# Data_Cable_REPLACMENT.net
KiCad netlist of a schematic drawn in EAGLE
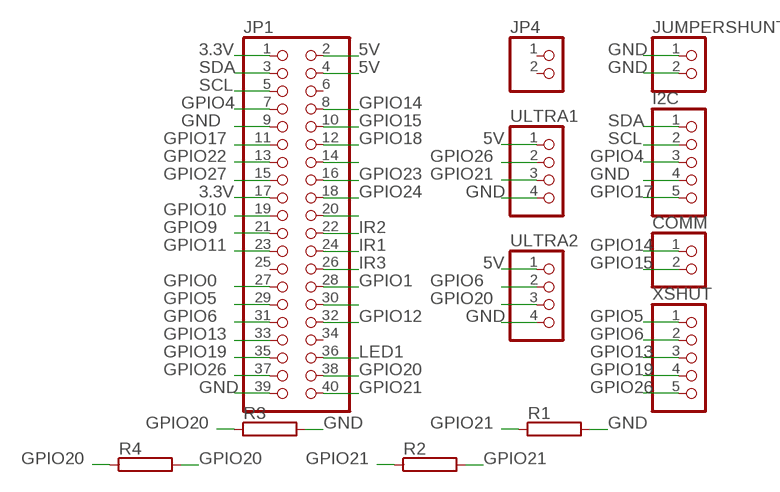
[diagram p0: schematic, sheet 1]

(export (version "E")
  (design (tool "Eeschema 10.0.6"))
  (components
    (comp (ref "COMM")
      (value "PINHD-1X2")
      (footprint "eagle-import:1X02")
      (libsource (lib "eagle-import") (part "PINHD-1X2"))
    )
    (comp (ref "I2C")
      (value "PINHD-1X5")
      (footprint "eagle-import:1X05")
      (libsource (lib "eagle-import") (part "PINHD-1X5"))
    )
    (comp (ref "JP1")
      (value "PINHD-2X20")
      (footprint "eagle-import:2X20")
      (libsource (lib "eagle-import") (part "PINHD-2X20"))
    )
    (comp (ref "JP4")
      (value "PINHD-1X2")
      (footprint "eagle-import:1X02")
      (libsource (lib "eagle-import") (part "PINHD-1X2"))
    )
    (comp (ref "JUMPERSHUNT")
      (value "PINHD-1X2")
      (footprint "eagle-import:1X02")
      (libsource (lib "eagle-import") (part "PINHD-1X2"))
    )
    (comp (ref "R1")
      (value "RHPS58")
      (footprint "eagle-import:HPS58")
      (libsource (lib "eagle-import") (part "RHPS58"))
    )
    (comp (ref "R2")
      (value "RHPS58")
      (footprint "eagle-import:HPS58")
      (libsource (lib "eagle-import") (part "RHPS58"))
    )
    (comp (ref "R3")
      (value "RHPS58")
      (footprint "eagle-import:HPS58")
      (libsource (lib "eagle-import") (part "RHPS58"))
    )
    (comp (ref "R4")
      (value "RHPS58")
      (footprint "eagle-import:HPS58")
      (libsource (lib "eagle-import") (part "RHPS58"))
    )
    (comp (ref "ULTRA1")
      (value "PINHD-1X4")
      (footprint "eagle-import:1X04")
      (libsource (lib "eagle-import") (part "PINHD-1X4"))
    )
    (comp (ref "ULTRA2")
      (value "PINHD-1X4")
      (footprint "eagle-import:1X04")
      (libsource (lib "eagle-import") (part "PINHD-1X4"))
    )
    (comp (ref "XSHUT")
      (value "PINHD-1X5")
      (footprint "eagle-import:1X05")
      (libsource (lib "eagle-import") (part "PINHD-1X5"))
    )
  )
  (nets
    (net (code "1") (name "/3.3V") (class "Default")
      (node (ref "JP1") (pin "1") (pinfunction "1_1") (pintype "passive"))
      (node (ref "JP1") (pin "17") (pinfunction "17_17") (pintype "passive"))
    )
    (net (code "2") (name "/5V") (class "Default")
      (node (ref "JP1") (pin "2") (pinfunction "2_2") (pintype "passive"))
      (node (ref "JP1") (pin "4") (pinfunction "4_4") (pintype "passive"))
      (node (ref "ULTRA1") (pin "1") (pinfunction "1_1") (pintype "passive"))
      (node (ref "ULTRA2") (pin "1") (pinfunction "1_1") (pintype "passive"))
    )
    (net (code "3") (name "/GND") (class "Default")
      (node (ref "I2C") (pin "4") (pinfunction "4_4") (pintype "passive"))
      (node (ref "JP1") (pin "39") (pinfunction "39_39") (pintype "passive"))
      (node (ref "JP1") (pin "9") (pinfunction "9_9") (pintype "passive"))
      (node (ref "JUMPERSHUNT") (pin "1") (pinfunction "1_1") (pintype "passive"))
      (node (ref "JUMPERSHUNT") (pin "2") (pinfunction "2_2") (pintype "passive"))
      (node (ref "R1") (pin "2") (pinfunction "2_2") (pintype "passive"))
      (node (ref "R3") (pin "2") (pinfunction "2_2") (pintype "passive"))
      (node (ref "ULTRA1") (pin "4") (pinfunction "4_4") (pintype "passive"))
      (node (ref "ULTRA2") (pin "4") (pinfunction "4_4") (pintype "passive"))
    )
    (net (code "4") (name "/GPIO0") (class "Default")
      (node (ref "JP1") (pin "27") (pinfunction "27_27") (pintype "passive"))
    )
    (net (code "5") (name "/GPIO1") (class "Default")
      (node (ref "JP1") (pin "28") (pinfunction "28_28") (pintype "passive"))
    )
    (net (code "6") (name "/GPIO4") (class "Default")
      (node (ref "I2C") (pin "3") (pinfunction "3_3") (pintype "passive"))
      (node (ref "JP1") (pin "7") (pinfunction "7_7") (pintype "passive"))
    )
    (net (code "7") (name "/GPIO5") (class "Default")
      (node (ref "JP1") (pin "29") (pinfunction "29_29") (pintype "passive"))
      (node (ref "XSHUT") (pin "1") (pinfunction "1_1") (pintype "passive"))
    )
    (net (code "8") (name "/GPIO6") (class "Default")
      (node (ref "JP1") (pin "31") (pinfunction "31_31") (pintype "passive"))
      (node (ref "ULTRA2") (pin "2") (pinfunction "2_2") (pintype "passive"))
      (node (ref "XSHUT") (pin "2") (pinfunction "2_2") (pintype "passive"))
    )
    (net (code "9") (name "/GPIO9") (class "Default")
      (node (ref "JP1") (pin "21") (pinfunction "21_21") (pintype "passive"))
    )
    (net (code "10") (name "/GPIO10") (class "Default")
      (node (ref "JP1") (pin "19") (pinfunction "19_19") (pintype "passive"))
    )
    (net (code "11") (name "/GPIO11") (class "Default")
      (node (ref "JP1") (pin "23") (pinfunction "23_23") (pintype "passive"))
    )
    (net (code "12") (name "/GPIO12") (class "Default")
      (node (ref "JP1") (pin "32") (pinfunction "32_32") (pintype "passive"))
    )
    (net (code "13") (name "/GPIO13") (class "Default")
      (node (ref "JP1") (pin "33") (pinfunction "33_33") (pintype "passive"))
      (node (ref "XSHUT") (pin "3") (pinfunction "3_3") (pintype "passive"))
    )
    (net (code "14") (name "/GPIO14") (class "Default")
      (node (ref "COMM") (pin "1") (pinfunction "1_1") (pintype "passive"))
      (node (ref "JP1") (pin "8") (pinfunction "8_8") (pintype "passive"))
    )
    (net (code "15") (name "/GPIO15") (class "Default")
      (node (ref "COMM") (pin "2") (pinfunction "2_2") (pintype "passive"))
      (node (ref "JP1") (pin "10") (pinfunction "10_10") (pintype "passive"))
    )
    (net (code "16") (name "/GPIO17") (class "Default")
      (node (ref "I2C") (pin "5") (pinfunction "5_5") (pintype "passive"))
      (node (ref "JP1") (pin "11") (pinfunction "11_11") (pintype "passive"))
    )
    (net (code "17") (name "/GPIO18") (class "Default")
      (node (ref "JP1") (pin "12") (pinfunction "12_12") (pintype "passive"))
    )
    (net (code "18") (name "/GPIO19") (class "Default")
      (node (ref "JP1") (pin "35") (pinfunction "35_35") (pintype "passive"))
      (node (ref "XSHUT") (pin "4") (pinfunction "4_4") (pintype "passive"))
    )
    (net (code "19") (name "/GPIO20") (class "Default")
      (node (ref "JP1") (pin "38") (pinfunction "38_38") (pintype "passive"))
      (node (ref "R3") (pin "1") (pinfunction "1_1") (pintype "passive"))
      (node (ref "R4") (pin "1") (pinfunction "1_1") (pintype "passive"))
      (node (ref "R4") (pin "2") (pinfunction "2_2") (pintype "passive"))
      (node (ref "ULTRA2") (pin "3") (pinfunction "3_3") (pintype "passive"))
    )
    (net (code "20") (name "/GPIO21") (class "Default")
      (node (ref "JP1") (pin "40") (pinfunction "40_40") (pintype "passive"))
      (node (ref "R1") (pin "1") (pinfunction "1_1") (pintype "passive"))
      (node (ref "R2") (pin "1") (pinfunction "1_1") (pintype "passive"))
      (node (ref "R2") (pin "2") (pinfunction "2_2") (pintype "passive"))
      (node (ref "ULTRA1") (pin "3") (pinfunction "3_3") (pintype "passive"))
    )
    (net (code "21") (name "/GPIO22") (class "Default")
      (node (ref "JP1") (pin "13") (pinfunction "13_13") (pintype "passive"))
    )
    (net (code "22") (name "/GPIO23") (class "Default")
      (node (ref "JP1") (pin "16") (pinfunction "16_16") (pintype "passive"))
    )
    (net (code "23") (name "/GPIO24") (class "Default")
      (node (ref "JP1") (pin "18") (pinfunction "18_18") (pintype "passive"))
    )
    (net (code "24") (name "/GPIO26") (class "Default")
      (node (ref "JP1") (pin "37") (pinfunction "37_37") (pintype "passive"))
      (node (ref "ULTRA1") (pin "2") (pinfunction "2_2") (pintype "passive"))
      (node (ref "XSHUT") (pin "5") (pinfunction "5_5") (pintype "passive"))
    )
    (net (code "25") (name "/GPIO27") (class "Default")
      (node (ref "JP1") (pin "15") (pinfunction "15_15") (pintype "passive"))
    )
    (net (code "26") (name "/IR1") (class "Default")
      (node (ref "JP1") (pin "24") (pinfunction "24_24") (pintype "passive"))
    )
    (net (code "27") (name "/IR2") (class "Default")
      (node (ref "JP1") (pin "22") (pinfunction "22_22") (pintype "passive"))
    )
    (net (code "28") (name "/IR3") (class "Default")
      (node (ref "JP1") (pin "26") (pinfunction "26_26") (pintype "passive"))
    )
    (net (code "29") (name "/LED1") (class "Default")
      (node (ref "JP1") (pin "36") (pinfunction "36_36") (pintype "passive"))
    )
    (net (code "30") (name "/SCL") (class "Default")
      (node (ref "I2C") (pin "2") (pinfunction "2_2") (pintype "passive"))
      (node (ref "JP1") (pin "5") (pinfunction "5_5") (pintype "passive"))
    )
    (net (code "31") (name "/SDA") (class "Default")
      (node (ref "I2C") (pin "1") (pinfunction "1_1") (pintype "passive"))
      (node (ref "JP1") (pin "3") (pinfunction "3_3") (pintype "passive"))
    )
    (net (code "32") (name "unconnected-(JP1-Pad6)") (class "Default")
      (node (ref "JP1") (pin "6") (pinfunction "6_6") (pintype "passive"))
    )
    (net (code "33") (name "unconnected-(JP1-Pad14)") (class "Default")
      (node (ref "JP1") (pin "14") (pinfunction "14_14") (pintype "passive"))
    )
    (net (code "34") (name "unconnected-(JP1-Pad20)") (class "Default")
      (node (ref "JP1") (pin "20") (pinfunction "20_20") (pintype "passive"))
    )
    (net (code "35") (name "unconnected-(JP1-Pad25)") (class "Default")
      (node (ref "JP1") (pin "25") (pinfunction "25_25") (pintype "passive"))
    )
    (net (code "36") (name "unconnected-(JP1-Pad30)") (class "Default")
      (node (ref "JP1") (pin "30") (pinfunction "30_30") (pintype "passive"))
    )
    (net (code "37") (name "unconnected-(JP1-Pad34)") (class "Default")
      (node (ref "JP1") (pin "34") (pinfunction "34_34") (pintype "passive"))
    )
    (net (code "38") (name "unconnected-(JP4-Pad1)") (class "Default")
      (node (ref "JP4") (pin "1") (pinfunction "1_1") (pintype "passive"))
    )
    (net (code "39") (name "unconnected-(JP4-Pad2)") (class "Default")
      (node (ref "JP4") (pin "2") (pinfunction "2_2") (pintype "passive"))
    )
  )
)
